# PPM2DSM.net
KiCad netlist of a schematic drawn in EAGLE
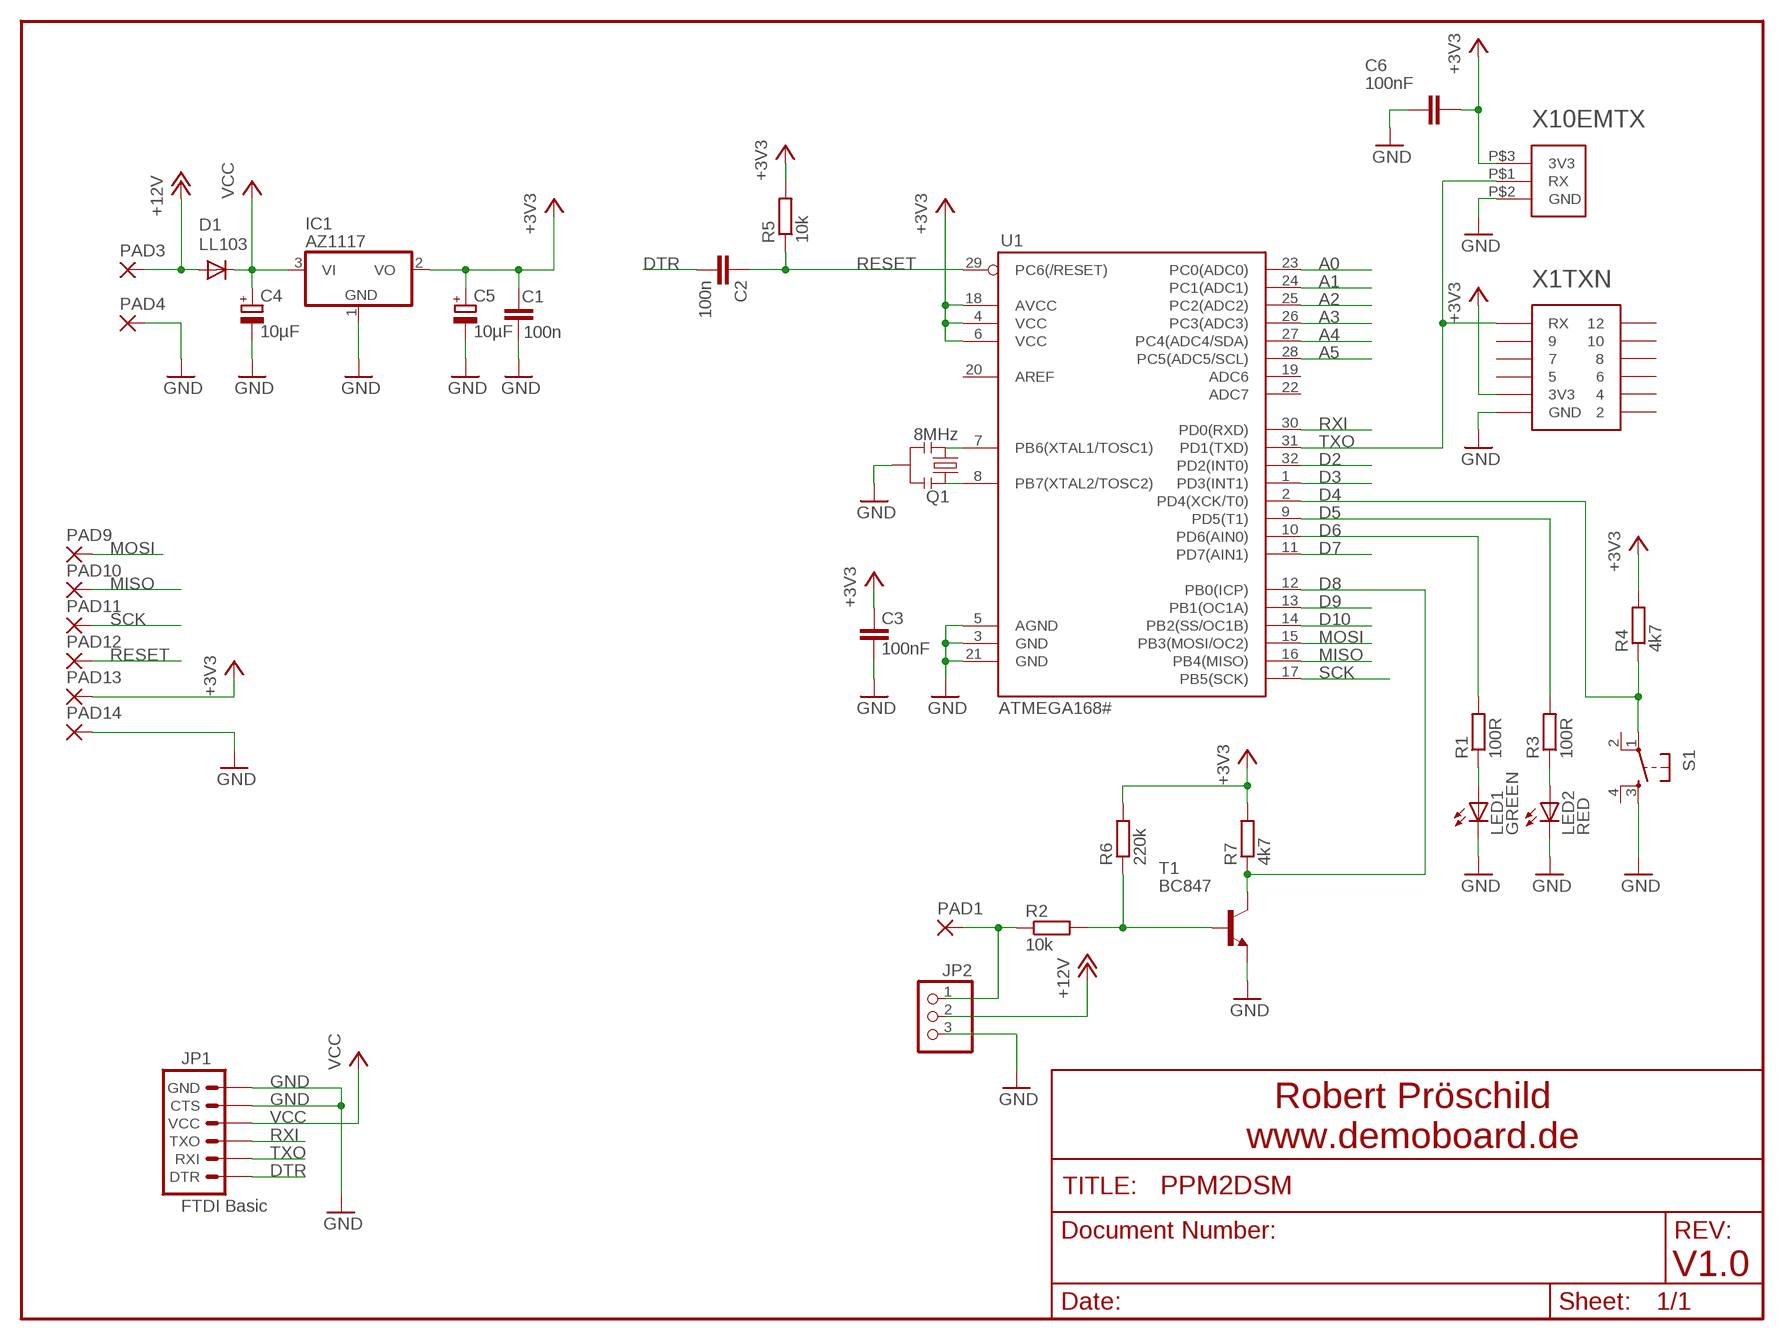
[diagram p0: schematic, sheet 1]

(export (version "E")
  (design (tool "Eeschema 10.0.6"))
  (components
    (comp (ref "C1")
      (value "100n")
      (footprint "eagle-import:C0805")
      (libsource (lib "eagle-import") (part "C-EUC0805"))
    )
    (comp (ref "C2")
      (value "100n")
      (footprint "eagle-import:C0805")
      (libsource (lib "eagle-import") (part "C-EUC0805"))
    )
    (comp (ref "C3")
      (value "100nF")
      (footprint "eagle-import:C0805")
      (libsource (lib "eagle-import") (part "C-EUC0805"))
    )
    (comp (ref "C4")
      (value "10µF")
      (footprint "eagle-import:CT6032")
      (libsource (lib "eagle-import") (part "CPOL-EUCT6032"))
    )
    (comp (ref "C5")
      (value "10µF")
      (footprint "eagle-import:CT6032")
      (libsource (lib "eagle-import") (part "CPOL-EUCT6032"))
    )
    (comp (ref "C6")
      (value "100nF")
      (footprint "eagle-import:C0805")
      (libsource (lib "eagle-import") (part "C-EUC0805"))
    )
    (comp (ref "D1")
      (value "LL103")
      (footprint "eagle-import:MINIMELF")
      (libsource (lib "eagle-import") (part "DIODE-MINIMELF"))
    )
    (comp (ref "IC1")
      (value "AZ1117")
      (footprint "eagle-import:SOT223")
      (libsource (lib "eagle-import") (part "AZ1117"))
    )
    (comp (ref "IC2")
      (value "X10EMTX")
      (footprint "eagle-import:X10EMTX")
      (libsource (lib "eagle-import") (part "X10EMTX"))
    )
    (comp (ref "IC3")
      (value "X1TX0")
      (footprint "eagle-import:X1TX0")
      (libsource (lib "eagle-import") (part "X1TX0"))
    )
    (comp (ref "JP1")
      (value "FTDI Basic")
      (footprint "eagle-import:1X06")
      (libsource (lib "eagle-import") (part "ARDUINO_SERIAL_PROGRAMPTH"))
    )
    (comp (ref "JP2")
      (value "PINHD-1X3/90")
      (footprint "eagle-import:1X03_90")
      (libsource (lib "eagle-import") (part "PINHD-1X3/90"))
    )
    (comp (ref "LED1")
      (value "GREEN")
      (footprint "eagle-import:CHIPLED_1206")
      (libsource (lib "eagle-import") (part "LEDCHIPLED_1206"))
    )
    (comp (ref "LED2")
      (value "RED")
      (footprint "eagle-import:CHIPLED_1206")
      (libsource (lib "eagle-import") (part "LEDCHIPLED_1206"))
    )
    (comp (ref "PAD1")
      (value "SMD5")
      (footprint "eagle-import:SMD2,54-5,08")
      (libsource (lib "eagle-import") (part "SMD5"))
    )
    (comp (ref "PAD3")
      (value "SMD5")
      (footprint "eagle-import:SMD2,54-5,08")
      (libsource (lib "eagle-import") (part "SMD5"))
    )
    (comp (ref "PAD4")
      (value "SMD5")
      (footprint "eagle-import:SMD2,54-5,08")
      (libsource (lib "eagle-import") (part "SMD5"))
    )
    (comp (ref "PAD9")
      (value "1,6/0,9")
      (footprint "eagle-import:1,6_0,9")
      (libsource (lib "eagle-import") (part "1,6/0,9"))
    )
    (comp (ref "PAD10")
      (value "1,6/0,9")
      (footprint "eagle-import:1,6_0,9")
      (libsource (lib "eagle-import") (part "1,6/0,9"))
    )
    (comp (ref "PAD11")
      (value "1,6/0,9")
      (footprint "eagle-import:1,6_0,9")
      (libsource (lib "eagle-import") (part "1,6/0,9"))
    )
    (comp (ref "PAD12")
      (value "1,6/0,9")
      (footprint "eagle-import:1,6_0,9")
      (libsource (lib "eagle-import") (part "1,6/0,9"))
    )
    (comp (ref "PAD13")
      (value "1,6/0,9")
      (footprint "eagle-import:1,6_0,9")
      (libsource (lib "eagle-import") (part "1,6/0,9"))
    )
    (comp (ref "PAD14")
      (value "1,6/0,9")
      (footprint "eagle-import:1,6_0,9")
      (libsource (lib "eagle-import") (part "1,6/0,9"))
    )
    (comp (ref "Q1")
      (value "8MHz")
      (footprint "eagle-import:RESONATOR-SMD")
      (libsource (lib "eagle-import") (part "RESONATORSMD"))
    )
    (comp (ref "R1")
      (value "100R")
      (footprint "eagle-import:R0805")
      (libsource (lib "eagle-import") (part "R-EU_R0805"))
    )
    (comp (ref "R2")
      (value "10k")
      (footprint "eagle-import:R0805")
      (libsource (lib "eagle-import") (part "R-EU_R0805"))
    )
    (comp (ref "R3")
      (value "100R")
      (footprint "eagle-import:R0805")
      (libsource (lib "eagle-import") (part "R-EU_R0805"))
    )
    (comp (ref "R4")
      (value "4k7")
      (footprint "eagle-import:R0805")
      (libsource (lib "eagle-import") (part "R-EU_R0805"))
    )
    (comp (ref "R5")
      (value "10k")
      (footprint "eagle-import:R0805")
      (libsource (lib "eagle-import") (part "R-EU_R0805"))
    )
    (comp (ref "R6")
      (value "220k")
      (footprint "eagle-import:R0805")
      (libsource (lib "eagle-import") (part "R-EU_R0805"))
    )
    (comp (ref "R7")
      (value "4k7")
      (footprint "eagle-import:R0805")
      (libsource (lib "eagle-import") (part "R-EU_R0805"))
    )
    (comp (ref "S1")
      (value "LSG")
      (footprint "eagle-import:SCHURTER_LSG")
      (libsource (lib "eagle-import") (part "LSG"))
    )
    (comp (ref "T1")
      (value "BC847")
      (footprint "eagle-import:SOT23")
      (libsource (lib "eagle-import") (part "BC847"))
    )
    (comp (ref "U1")
      (value "ATMEGA168#")
      (footprint "eagle-import:TQFP32-08")
      (libsource (lib "eagle-import") (part "ATMEGA168"))
    )
  )
  (nets
    (net (code "1") (name "+3V3") (class "Default")
      (node (ref "C1") (pin "2") (pinfunction "2_2") (pintype "passive"))
      (node (ref "C3") (pin "2") (pinfunction "2_2") (pintype "passive"))
      (node (ref "C5") (pin "+") (pinfunction "+_+") (pintype "passive"))
      (node (ref "C6") (pin "2") (pinfunction "2_2") (pintype "passive"))
      (node (ref "IC1") (pin "2") (pinfunction "VO_2") (pintype "passive"))
      (node (ref "IC2") (pin "P$3") (pinfunction "3V3_P$3") (pintype "power_in"))
      (node (ref "IC3") (pin "3") (pinfunction "3V3_3") (pintype "bidirectional"))
      (node (ref "PAD13") (pin "1") (pinfunction "P_1") (pintype "passive"))
      (node (ref "R4") (pin "2") (pinfunction "2_2") (pintype "passive"))
      (node (ref "R5") (pin "2") (pinfunction "2_2") (pintype "passive"))
      (node (ref "R6") (pin "2") (pinfunction "2_2") (pintype "passive"))
      (node (ref "R7") (pin "2") (pinfunction "2_2") (pintype "passive"))
      (node (ref "U1") (pin "18") (pinfunction "AVCC_18") (pintype "bidirectional"))
      (node (ref "U1") (pin "4") (pinfunction "VCC_4") (pintype "bidirectional"))
      (node (ref "U1") (pin "6") (pinfunction "VCC_6") (pintype "bidirectional"))
    )
    (net (code "2") (name "+12V") (class "Default")
      (node (ref "D1") (pin "A") (pinfunction "A_A") (pintype "passive"))
      (node (ref "JP2") (pin "2") (pinfunction "2_2") (pintype "passive"))
      (node (ref "PAD3") (pin "1") (pinfunction "P_1") (pintype "passive"))
    )
    (net (code "3") (name "/2") (class "Default")
      (node (ref "IC3") (pin "2") (pinfunction "2_2") (pintype "power_in"))
    )
    (net (code "4") (name "/4") (class "Default")
      (node (ref "IC3") (pin "4") (pinfunction "4_4") (pintype "power_in"))
    )
    (net (code "5") (name "/A0") (class "Default")
      (node (ref "U1") (pin "23") (pinfunction "PC0(ADC0)_23") (pintype "bidirectional"))
    )
    (net (code "6") (name "/A1") (class "Default")
      (node (ref "U1") (pin "24") (pinfunction "PC1(ADC1)_24") (pintype "bidirectional"))
    )
    (net (code "7") (name "/A2") (class "Default")
      (node (ref "U1") (pin "25") (pinfunction "PC2(ADC2)_25") (pintype "bidirectional"))
    )
    (net (code "8") (name "/A3") (class "Default")
      (node (ref "U1") (pin "26") (pinfunction "PC3(ADC3)_26") (pintype "bidirectional"))
    )
    (net (code "9") (name "/A4") (class "Default")
      (node (ref "U1") (pin "27") (pinfunction "PC4(ADC4/SDA)_27") (pintype "bidirectional"))
    )
    (net (code "10") (name "/A5") (class "Default")
      (node (ref "U1") (pin "28") (pinfunction "PC5(ADC5/SCL)_28") (pintype "bidirectional"))
    )
    (net (code "11") (name "/D2") (class "Default")
      (node (ref "U1") (pin "32") (pinfunction "PD2(INT0)_32") (pintype "bidirectional"))
    )
    (net (code "12") (name "/D3") (class "Default")
      (node (ref "U1") (pin "1") (pinfunction "PD3(INT1)_1") (pintype "bidirectional"))
    )
    (net (code "13") (name "/D4") (class "Default")
      (node (ref "R4") (pin "1") (pinfunction "1_1") (pintype "passive"))
      (node (ref "S1") (pin "1") (pinfunction "P_1") (pintype "passive"))
      (node (ref "U1") (pin "2") (pinfunction "PD4(XCK/T0)_2") (pintype "bidirectional"))
    )
    (net (code "14") (name "/D5") (class "Default")
      (node (ref "R3") (pin "2") (pinfunction "2_2") (pintype "passive"))
      (node (ref "U1") (pin "9") (pinfunction "PD5(T1)_9") (pintype "bidirectional"))
    )
    (net (code "15") (name "/D6") (class "Default")
      (node (ref "R1") (pin "2") (pinfunction "2_2") (pintype "passive"))
      (node (ref "U1") (pin "10") (pinfunction "PD6(AIN0)_10") (pintype "bidirectional"))
    )
    (net (code "16") (name "/D7") (class "Default")
      (node (ref "U1") (pin "11") (pinfunction "PD7(AIN1)_11") (pintype "bidirectional"))
    )
    (net (code "17") (name "/D8") (class "Default")
      (node (ref "R7") (pin "1") (pinfunction "1_1") (pintype "passive"))
      (node (ref "T1") (pin "3") (pinfunction "C_3") (pintype "passive"))
      (node (ref "U1") (pin "12") (pinfunction "PB0(ICP)_12") (pintype "bidirectional"))
    )
    (net (code "18") (name "/D9") (class "Default")
      (node (ref "U1") (pin "13") (pinfunction "PB1(OC1A)_13") (pintype "bidirectional"))
    )
    (net (code "19") (name "/D10") (class "Default")
      (node (ref "U1") (pin "14") (pinfunction "PB2(SS/OC1B)_14") (pintype "bidirectional"))
    )
    (net (code "20") (name "/DTR") (class "Default")
      (node (ref "C2") (pin "2") (pinfunction "2_2") (pintype "passive"))
      (node (ref "JP1") (pin "1") (pinfunction "DTR_1") (pintype "passive"))
    )
    (net (code "21") (name "/MISO") (class "Default")
      (node (ref "PAD10") (pin "1") (pinfunction "P_1") (pintype "passive"))
      (node (ref "U1") (pin "16") (pinfunction "PB4(MISO)_16") (pintype "bidirectional"))
    )
    (net (code "22") (name "/MOSI") (class "Default")
      (node (ref "PAD9") (pin "1") (pinfunction "P_1") (pintype "passive"))
      (node (ref "U1") (pin "15") (pinfunction "PB3(MOSI/OC2)_15") (pintype "bidirectional"))
    )
    (net (code "23") (name "/RESET") (class "Default")
      (node (ref "C2") (pin "1") (pinfunction "1_1") (pintype "passive"))
      (node (ref "PAD12") (pin "1") (pinfunction "P_1") (pintype "passive"))
      (node (ref "R5") (pin "1") (pinfunction "1_1") (pintype "passive"))
      (node (ref "U1") (pin "29") (pinfunction "PC6(/RESET)_29") (pintype "bidirectional"))
    )
    (net (code "24") (name "/RXI") (class "Default")
      (node (ref "JP1") (pin "3") (pinfunction "TXO_3") (pintype "passive"))
      (node (ref "U1") (pin "30") (pinfunction "PD0(RXD)_30") (pintype "bidirectional"))
    )
    (net (code "25") (name "/SCK") (class "Default")
      (node (ref "PAD11") (pin "1") (pinfunction "P_1") (pintype "passive"))
      (node (ref "U1") (pin "17") (pinfunction "PB5(SCK)_17") (pintype "bidirectional"))
    )
    (net (code "26") (name "/TXO") (class "Default")
      (node (ref "IC2") (pin "P$1") (pinfunction "RX_P$1") (pintype "input"))
      (node (ref "IC3") (pin "11") (pinfunction "RX_11") (pintype "bidirectional"))
      (node (ref "JP1") (pin "2") (pinfunction "RXI_2") (pintype "passive"))
      (node (ref "U1") (pin "31") (pinfunction "PD1(TXD)_31") (pintype "bidirectional"))
    )
    (net (code "27") (name "GND") (class "Default")
      (node (ref "C1") (pin "1") (pinfunction "1_1") (pintype "passive"))
      (node (ref "C3") (pin "1") (pinfunction "1_1") (pintype "passive"))
      (node (ref "C4") (pin "-") (pinfunction "-_-") (pintype "passive"))
      (node (ref "C5") (pin "-") (pinfunction "-_-") (pintype "passive"))
      (node (ref "C6") (pin "1") (pinfunction "1_1") (pintype "passive"))
      (node (ref "IC1") (pin "1") (pinfunction "GND_1") (pintype "passive"))
      (node (ref "IC2") (pin "P$2") (pinfunction "GND_P$2") (pintype "power_in"))
      (node (ref "IC3") (pin "1") (pinfunction "GND_1") (pintype "bidirectional"))
      (node (ref "JP1") (pin "5") (pinfunction "CTS_5") (pintype "passive"))
      (node (ref "JP1") (pin "6") (pinfunction "GND_6") (pintype "passive"))
      (node (ref "JP2") (pin "3") (pinfunction "3_3") (pintype "passive"))
      (node (ref "LED1") (pin "C") (pinfunction "C_C") (pintype "passive"))
      (node (ref "LED2") (pin "C") (pinfunction "C_C") (pintype "passive"))
      (node (ref "PAD14") (pin "1") (pinfunction "P_1") (pintype "passive"))
      (node (ref "PAD4") (pin "1") (pinfunction "P_1") (pintype "passive"))
      (node (ref "Q1") (pin "2") (pinfunction "2_2") (pintype "passive"))
      (node (ref "S1") (pin "3") (pinfunction "S_3") (pintype "passive"))
      (node (ref "T1") (pin "2") (pinfunction "E_2") (pintype "passive"))
      (node (ref "U1") (pin "21") (pinfunction "GND_21") (pintype "bidirectional"))
      (node (ref "U1") (pin "3") (pinfunction "GND_3") (pintype "bidirectional"))
      (node (ref "U1") (pin "5") (pinfunction "AGND_5") (pintype "bidirectional"))
    )
    (net (code "28") (name "Net-(LED1-PadA)") (class "Default")
      (node (ref "LED1") (pin "A") (pinfunction "A_A") (pintype "passive"))
      (node (ref "R1") (pin "1") (pinfunction "1_1") (pintype "passive"))
    )
    (net (code "29") (name "Net-(LED2-PadA)") (class "Default")
      (node (ref "LED2") (pin "A") (pinfunction "A_A") (pintype "passive"))
      (node (ref "R3") (pin "1") (pinfunction "1_1") (pintype "passive"))
    )
    (net (code "30") (name "Net-(PAD1-P)") (class "Default")
      (node (ref "JP2") (pin "1") (pinfunction "1_1") (pintype "passive"))
      (node (ref "PAD1") (pin "1") (pinfunction "P_1") (pintype "passive"))
      (node (ref "R2") (pin "1") (pinfunction "1_1") (pintype "passive"))
    )
    (net (code "31") (name "Net-(T1-B)") (class "Default")
      (node (ref "R2") (pin "2") (pinfunction "2_2") (pintype "passive"))
      (node (ref "R6") (pin "1") (pinfunction "1_1") (pintype "passive"))
      (node (ref "T1") (pin "1") (pinfunction "B_1") (pintype "passive"))
    )
    (net (code "32") (name "Net-(U1-PB6(XTAL1{slash}TOSC1))") (class "Default")
      (node (ref "Q1") (pin "3") (pinfunction "3_3") (pintype "passive"))
      (node (ref "U1") (pin "7") (pinfunction "PB6(XTAL1/TOSC1)_7") (pintype "bidirectional"))
    )
    (net (code "33") (name "Net-(U1-PB7(XTAL2{slash}TOSC2))") (class "Default")
      (node (ref "Q1") (pin "1") (pinfunction "1_1") (pintype "passive"))
      (node (ref "U1") (pin "8") (pinfunction "PB7(XTAL2/TOSC2)_8") (pintype "bidirectional"))
    )
    (net (code "34") (name "VCC") (class "Default")
      (node (ref "C4") (pin "+") (pinfunction "+_+") (pintype "passive"))
      (node (ref "D1") (pin "C") (pinfunction "C_C") (pintype "passive"))
      (node (ref "IC1") (pin "3") (pinfunction "VI_3") (pintype "input"))
      (node (ref "JP1") (pin "4") (pinfunction "VCC_4") (pintype "passive"))
    )
    (net (code "35") (name "unconnected-(IC3-Pad5)") (class "Default")
      (node (ref "IC3") (pin "5") (pinfunction "5_5") (pintype "bidirectional"))
    )
    (net (code "36") (name "unconnected-(IC3-Pad6)") (class "Default")
      (node (ref "IC3") (pin "6") (pinfunction "6_6") (pintype "bidirectional"))
    )
    (net (code "37") (name "unconnected-(IC3-Pad7)") (class "Default")
      (node (ref "IC3") (pin "7") (pinfunction "7_7") (pintype "bidirectional"))
    )
    (net (code "38") (name "unconnected-(IC3-Pad8)") (class "Default")
      (node (ref "IC3") (pin "8") (pinfunction "8_8") (pintype "bidirectional"))
    )
    (net (code "39") (name "unconnected-(IC3-Pad9)") (class "Default")
      (node (ref "IC3") (pin "9") (pinfunction "9_9") (pintype "bidirectional"))
    )
    (net (code "40") (name "unconnected-(IC3-Pad10)") (class "Default")
      (node (ref "IC3") (pin "10") (pinfunction "10_10") (pintype "bidirectional"))
    )
    (net (code "41") (name "unconnected-(IC3-Pad12)") (class "Default")
      (node (ref "IC3") (pin "12") (pinfunction "12_12") (pintype "input"))
    )
    (net (code "42") (name "unconnected-(S1-P1-Pad2)") (class "Default")
      (node (ref "S1") (pin "2") (pinfunction "P1_2") (pintype "passive"))
    )
    (net (code "43") (name "unconnected-(S1-S1-Pad4)") (class "Default")
      (node (ref "S1") (pin "4") (pinfunction "S1_4") (pintype "passive"))
    )
    (net (code "44") (name "unconnected-(U1-ADC6-Pad19)") (class "Default")
      (node (ref "U1") (pin "19") (pinfunction "ADC6_19") (pintype "bidirectional"))
    )
    (net (code "45") (name "unconnected-(U1-ADC7-Pad22)") (class "Default")
      (node (ref "U1") (pin "22") (pinfunction "ADC7_22") (pintype "bidirectional"))
    )
    (net (code "46") (name "unconnected-(U1-AREF-Pad20)") (class "Default")
      (node (ref "U1") (pin "20") (pinfunction "AREF_20") (pintype "bidirectional"))
    )
  )
)
